# ELECTRO3.net
KiCad netlist of a schematic drawn in Altium Designer
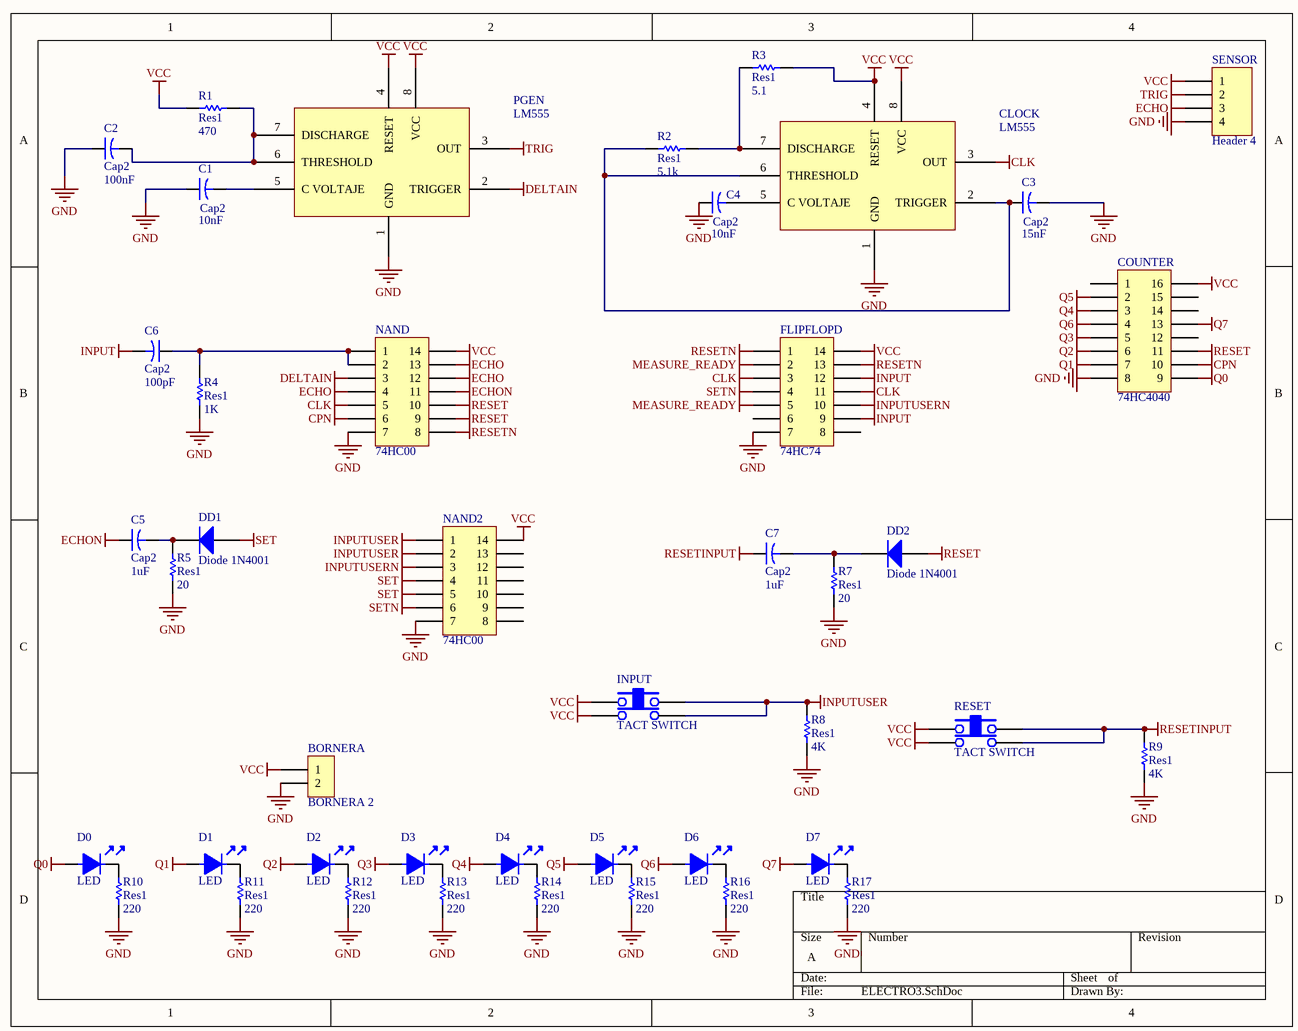
[diagram p0: ELECTRO3.SchDoc]

(export (version "E")
  (design (tool "Eeschema 10.0.6"))
  (components
    (comp (ref "BORNERA")
      (value "BORNERA 2")
      (footprint "BORNERA2")
      (libsource (lib "LIBEBAL") (part "BORNERA 2"))
    )
    (comp (ref "C1")
      (value "Cap2")
      (footprint "CAPR5-4X5")
      (description "Capacitor")
      (fields (field (name "ALTIUM_VALUE") "10nF") (field (name "PUBLISHER") "Altium Limited"))
      (libsource (lib "Miscellaneous Devices") (part "Cap2"))
    )
    (comp (ref "C2")
      (value "Cap2")
      (footprint "CAPR5-4X5")
      (description "Capacitor")
      (fields (field (name "ALTIUM_VALUE") "100nF") (field (name "PUBLISHER") "Altium Limited"))
      (libsource (lib "Miscellaneous Devices") (part "Cap2"))
    )
    (comp (ref "C3")
      (value "Cap2")
      (footprint "CAPR5-4X5")
      (description "Capacitor")
      (fields (field (name "ALTIUM_VALUE") "15nF") (field (name "PUBLISHER") "Altium Limited"))
      (libsource (lib "Miscellaneous Devices") (part "Cap2"))
    )
    (comp (ref "C4")
      (value "Cap2")
      (footprint "CAPR5-4X5")
      (description "Capacitor")
      (fields (field (name "ALTIUM_VALUE") "10nF") (field (name "PUBLISHER") "Altium Limited"))
      (libsource (lib "Miscellaneous Devices") (part "Cap2"))
    )
    (comp (ref "C5")
      (value "Cap2")
      (footprint "CAPR5-4X5")
      (description "Capacitor")
      (fields (field (name "ALTIUM_VALUE") "1uF") (field (name "PUBLISHER") "Altium Limited"))
      (libsource (lib "Miscellaneous Devices") (part "Cap2"))
    )
    (comp (ref "C6")
      (value "Cap2")
      (footprint "CAPR5-4X5")
      (description "Capacitor")
      (fields (field (name "ALTIUM_VALUE") "100pF") (field (name "PUBLISHER") "Altium Limited"))
      (libsource (lib "Miscellaneous Devices") (part "Cap2"))
    )
    (comp (ref "C7")
      (value "Cap2")
      (footprint "CAPR5-4X5")
      (description "Capacitor")
      (fields (field (name "ALTIUM_VALUE") "1uF") (field (name "PUBLISHER") "Altium Limited"))
      (libsource (lib "Miscellaneous Devices") (part "Cap2"))
    )
    (comp (ref "CLOCK")
      (value "LM555")
      (footprint "DIP8")
      (description "Timer")
      (libsource (lib "LIBEBAL") (part "LM555"))
    )
    (comp (ref "COUNTER")
      (value "74HC4040")
      (footprint "DIP16")
      (libsource (lib "LIBEBAL") (part "IC_DIP16"))
    )
    (comp (ref "D0") (value "LED") (footprint "LED3") (libsource (lib "LIBEBAL") (part "LED")))
    (comp (ref "D1") (value "LED") (footprint "LED3") (libsource (lib "LIBEBAL") (part "LED")))
    (comp (ref "D2") (value "LED") (footprint "LED3") (libsource (lib "LIBEBAL") (part "LED")))
    (comp (ref "D3") (value "LED") (footprint "LED3") (libsource (lib "LIBEBAL") (part "LED")))
    (comp (ref "D4") (value "LED") (footprint "LED3") (libsource (lib "LIBEBAL") (part "LED")))
    (comp (ref "D5") (value "LED") (footprint "LED3") (libsource (lib "LIBEBAL") (part "LED")))
    (comp (ref "D6") (value "LED") (footprint "LED3") (libsource (lib "LIBEBAL") (part "LED")))
    (comp (ref "D7") (value "LED") (footprint "LED3") (libsource (lib "LIBEBAL") (part "LED")))
    (comp (ref "DD1")
      (value "Diode 1N4001")
      (footprint "DO-41")
      (description "1 Amp General Purpose Rectifier")
      (fields (field (name "PUBLISHER") "Altium Limited"))
      (libsource (lib "Miscellaneous Devices") (part "Diode 1N4001"))
    )
    (comp (ref "DD2")
      (value "Diode 1N4001")
      (footprint "DO-41")
      (description "1 Amp General Purpose Rectifier")
      (fields (field (name "PUBLISHER") "Altium Limited"))
      (libsource (lib "Miscellaneous Devices") (part "Diode 1N4001"))
    )
    (comp (ref "FLIPFLOPD")
      (value "74HC74")
      (footprint "DIP14")
      (libsource (lib "LIBEBAL") (part "IC_DIP14"))
    )
    (comp (ref "INPUT")
      (value "TACT SWITCH")
      (footprint "TACTSWITCH")
      (libsource (lib "LIBEBAL") (part "TACT SWITCH"))
    )
    (comp (ref "NAND") (value "74HC00") (footprint "DIP14") (libsource (lib "LIBEBAL") (part "IC_DIP14")))
    (comp (ref "NAND2") (value "74HC00") (footprint "DIP14") (libsource (lib "LIBEBAL") (part "IC_DIP14")))
    (comp (ref "PGEN")
      (value "LM555")
      (footprint "DIP8")
      (description "Timer")
      (libsource (lib "LIBEBAL") (part "LM555"))
    )
    (comp (ref "R1")
      (value "Res1")
      (footprint "AXIAL-0.3")
      (description "Resistor")
      (fields (field (name "ALTIUM_VALUE") "470") (field (name "PUBLISHER") "Altium Limited"))
      (libsource (lib "Miscellaneous Devices") (part "Res1"))
    )
    (comp (ref "R2")
      (value "Res1")
      (footprint "AXIAL-0.3")
      (description "Resistor")
      (fields (field (name "ALTIUM_VALUE") "5.1k") (field (name "PUBLISHER") "Altium Limited"))
      (libsource (lib "Miscellaneous Devices") (part "Res1"))
    )
    (comp (ref "R3")
      (value "Res1")
      (footprint "AXIAL-0.3")
      (description "Resistor")
      (fields (field (name "ALTIUM_VALUE") "5.1") (field (name "PUBLISHER") "Altium Limited"))
      (libsource (lib "Miscellaneous Devices") (part "Res1"))
    )
    (comp (ref "R4")
      (value "Res1")
      (footprint "AXIAL-0.3")
      (description "Resistor")
      (fields (field (name "ALTIUM_VALUE") "1K") (field (name "PUBLISHER") "Altium Limited"))
      (libsource (lib "Miscellaneous Devices") (part "Res1"))
    )
    (comp (ref "R5")
      (value "Res1")
      (footprint "AXIAL-0.3")
      (description "Resistor")
      (fields (field (name "ALTIUM_VALUE") "20") (field (name "PUBLISHER") "Altium Limited"))
      (libsource (lib "Miscellaneous Devices") (part "Res1"))
    )
    (comp (ref "R7")
      (value "Res1")
      (footprint "AXIAL-0.3")
      (description "Resistor")
      (fields (field (name "ALTIUM_VALUE") "20") (field (name "PUBLISHER") "Altium Limited"))
      (libsource (lib "Miscellaneous Devices") (part "Res1"))
    )
    (comp (ref "R8")
      (value "Res1")
      (footprint "AXIAL-0.3")
      (description "Resistor")
      (fields (field (name "ALTIUM_VALUE") "4K") (field (name "PUBLISHER") "Altium Limited"))
      (libsource (lib "Miscellaneous Devices") (part "Res1"))
    )
    (comp (ref "R9")
      (value "Res1")
      (footprint "AXIAL-0.3")
      (description "Resistor")
      (fields (field (name "ALTIUM_VALUE") "4K") (field (name "PUBLISHER") "Altium Limited"))
      (libsource (lib "Miscellaneous Devices") (part "Res1"))
    )
    (comp (ref "R10")
      (value "Res1")
      (footprint "AXIAL-0.3")
      (description "Resistor")
      (fields (field (name "ALTIUM_VALUE") "220") (field (name "PUBLISHER") "Altium Limited"))
      (libsource (lib "Miscellaneous Devices") (part "Res1"))
    )
    (comp (ref "R11")
      (value "Res1")
      (footprint "AXIAL-0.3")
      (description "Resistor")
      (fields (field (name "ALTIUM_VALUE") "220") (field (name "PUBLISHER") "Altium Limited"))
      (libsource (lib "Miscellaneous Devices") (part "Res1"))
    )
    (comp (ref "R12")
      (value "Res1")
      (footprint "AXIAL-0.3")
      (description "Resistor")
      (fields (field (name "ALTIUM_VALUE") "220") (field (name "PUBLISHER") "Altium Limited"))
      (libsource (lib "Miscellaneous Devices") (part "Res1"))
    )
    (comp (ref "R13")
      (value "Res1")
      (footprint "AXIAL-0.3")
      (description "Resistor")
      (fields (field (name "ALTIUM_VALUE") "220") (field (name "PUBLISHER") "Altium Limited"))
      (libsource (lib "Miscellaneous Devices") (part "Res1"))
    )
    (comp (ref "R14")
      (value "Res1")
      (footprint "AXIAL-0.3")
      (description "Resistor")
      (fields (field (name "ALTIUM_VALUE") "220") (field (name "PUBLISHER") "Altium Limited"))
      (libsource (lib "Miscellaneous Devices") (part "Res1"))
    )
    (comp (ref "R15")
      (value "Res1")
      (footprint "AXIAL-0.3")
      (description "Resistor")
      (fields (field (name "ALTIUM_VALUE") "220") (field (name "PUBLISHER") "Altium Limited"))
      (libsource (lib "Miscellaneous Devices") (part "Res1"))
    )
    (comp (ref "R16")
      (value "Res1")
      (footprint "AXIAL-0.3")
      (description "Resistor")
      (fields (field (name "ALTIUM_VALUE") "220") (field (name "PUBLISHER") "Altium Limited"))
      (libsource (lib "Miscellaneous Devices") (part "Res1"))
    )
    (comp (ref "R17")
      (value "Res1")
      (footprint "AXIAL-0.3")
      (description "Resistor")
      (fields (field (name "ALTIUM_VALUE") "220") (field (name "PUBLISHER") "Altium Limited"))
      (libsource (lib "Miscellaneous Devices") (part "Res1"))
    )
    (comp (ref "RESET")
      (value "TACT SWITCH")
      (footprint "TACTSWITCH")
      (libsource (lib "LIBEBAL") (part "TACT SWITCH"))
    )
    (comp (ref "SENSOR")
      (value "Header 4")
      (footprint "HDR1X4")
      (description "Header, 4-Pin")
      (fields (field (name "PUBLISHER") "Altium Limited"))
      (libsource (lib "Miscellaneous Connectors") (part "Header 4"))
    )
  )
  (nets
    (net (code "1") (name "CLK") (class "Default")
      (node (ref "CLOCK") (pin "3") (pinfunction "OUT_3") (pintype "passive"))
      (node (ref "FLIPFLOPD") (pin "11") (pinfunction "11_11") (pintype "passive"))
      (node (ref "FLIPFLOPD") (pin "3") (pinfunction "3_3") (pintype "passive"))
      (node (ref "NAND") (pin "5") (pinfunction "5_5") (pintype "passive"))
    )
    (net (code "2") (name "CPN") (class "Default")
      (node (ref "COUNTER") (pin "10") (pinfunction "10_10") (pintype "passive"))
      (node (ref "NAND") (pin "6") (pinfunction "6_6") (pintype "passive"))
    )
    (net (code "3") (name "DELTAIN") (class "Default")
      (node (ref "NAND") (pin "3") (pinfunction "3_3") (pintype "passive"))
      (node (ref "PGEN") (pin "2") (pinfunction "TRIGGER_2") (pintype "passive"))
    )
    (net (code "4") (name "ECHO") (class "Default")
      (node (ref "NAND") (pin "12") (pinfunction "12_12") (pintype "passive"))
      (node (ref "NAND") (pin "13") (pinfunction "13_13") (pintype "passive"))
      (node (ref "NAND") (pin "4") (pinfunction "4_4") (pintype "passive"))
      (node (ref "SENSOR") (pin "3") (pinfunction "3_3") (pintype "passive"))
    )
    (net (code "5") (name "ECHON") (class "Default")
      (node (ref "C5") (pin "1") (pinfunction "1_1") (pintype "passive"))
      (node (ref "NAND") (pin "11") (pinfunction "11_11") (pintype "passive"))
    )
    (net (code "6") (name "GND") (class "Default")
      (node (ref "BORNERA") (pin "2") (pinfunction "2_2") (pintype "passive"))
      (node (ref "C1") (pin "1") (pinfunction "1_1") (pintype "passive"))
      (node (ref "C2") (pin "1") (pinfunction "1_1") (pintype "passive"))
      (node (ref "C3") (pin "2") (pinfunction "2_2") (pintype "passive"))
      (node (ref "C4") (pin "1") (pinfunction "1_1") (pintype "passive"))
      (node (ref "CLOCK") (pin "1") (pinfunction "GND_1") (pintype "passive"))
      (node (ref "COUNTER") (pin "8") (pinfunction "8_8") (pintype "passive"))
      (node (ref "FLIPFLOPD") (pin "7") (pinfunction "7_7") (pintype "passive"))
      (node (ref "NAND") (pin "7") (pinfunction "7_7") (pintype "passive"))
      (node (ref "NAND2") (pin "7") (pinfunction "7_7") (pintype "passive"))
      (node (ref "PGEN") (pin "1") (pinfunction "GND_1") (pintype "passive"))
      (node (ref "R10") (pin "1") (pinfunction "1_1") (pintype "passive"))
      (node (ref "R11") (pin "1") (pinfunction "1_1") (pintype "passive"))
      (node (ref "R12") (pin "1") (pinfunction "1_1") (pintype "passive"))
      (node (ref "R13") (pin "1") (pinfunction "1_1") (pintype "passive"))
      (node (ref "R14") (pin "1") (pinfunction "1_1") (pintype "passive"))
      (node (ref "R15") (pin "1") (pinfunction "1_1") (pintype "passive"))
      (node (ref "R16") (pin "1") (pinfunction "1_1") (pintype "passive"))
      (node (ref "R17") (pin "1") (pinfunction "1_1") (pintype "passive"))
      (node (ref "R4") (pin "2") (pinfunction "2_2") (pintype "passive"))
      (node (ref "R5") (pin "1") (pinfunction "1_1") (pintype "passive"))
      (node (ref "R7") (pin "1") (pinfunction "1_1") (pintype "passive"))
      (node (ref "R8") (pin "1") (pinfunction "1_1") (pintype "passive"))
      (node (ref "R9") (pin "1") (pinfunction "1_1") (pintype "passive"))
      (node (ref "SENSOR") (pin "4") (pinfunction "4_4") (pintype "passive"))
    )
    (net (code "7") (name "INPUT") (class "Default")
      (node (ref "C6") (pin "2") (pinfunction "2_2") (pintype "passive"))
      (node (ref "FLIPFLOPD") (pin "12") (pinfunction "12_12") (pintype "passive"))
      (node (ref "FLIPFLOPD") (pin "9") (pinfunction "9_9") (pintype "passive"))
    )
    (net (code "8") (name "INPUTUSER") (class "Default")
      (node (ref "INPUT") (pin "3") (pinfunction "3_3") (pintype "passive"))
      (node (ref "INPUT") (pin "4") (pinfunction "4_4") (pintype "passive"))
      (node (ref "NAND2") (pin "1") (pinfunction "1_1") (pintype "passive"))
      (node (ref "NAND2") (pin "2") (pinfunction "2_2") (pintype "passive"))
      (node (ref "R8") (pin "2") (pinfunction "2_2") (pintype "passive"))
    )
    (net (code "9") (name "INPUTUSERN") (class "Default")
      (node (ref "FLIPFLOPD") (pin "10") (pinfunction "10_10") (pintype "passive"))
      (node (ref "NAND2") (pin "3") (pinfunction "3_3") (pintype "passive"))
    )
    (net (code "10") (name "MEASURE_READY") (class "Default")
      (node (ref "FLIPFLOPD") (pin "2") (pinfunction "2_2") (pintype "passive"))
      (node (ref "FLIPFLOPD") (pin "5") (pinfunction "5_5") (pintype "passive"))
    )
    (net (code "11") (name "Net-(C6-Pad1)") (class "Default")
      (node (ref "C6") (pin "1") (pinfunction "1_1") (pintype "passive"))
      (node (ref "NAND") (pin "1") (pinfunction "1_1") (pintype "passive"))
      (node (ref "NAND") (pin "2") (pinfunction "2_2") (pintype "passive"))
      (node (ref "R4") (pin "1") (pinfunction "1_1") (pintype "passive"))
    )
    (net (code "12") (name "Net-(CLOCK-C_VOLTAJE)") (class "Default")
      (node (ref "C4") (pin "2") (pinfunction "2_2") (pintype "passive"))
      (node (ref "CLOCK") (pin "5") (pinfunction "C_VOLTAJE_5") (pintype "passive"))
    )
    (net (code "13") (name "Net-(CLOCK-DISCHARGE)") (class "Default")
      (node (ref "CLOCK") (pin "7") (pinfunction "DISCHARGE_7") (pintype "passive"))
      (node (ref "R2") (pin "2") (pinfunction "2_2") (pintype "passive"))
      (node (ref "R3") (pin "1") (pinfunction "1_1") (pintype "passive"))
    )
    (net (code "14") (name "Net-(CLOCK-THRESHOLD)") (class "Default")
      (node (ref "C3") (pin "1") (pinfunction "1_1") (pintype "passive"))
      (node (ref "CLOCK") (pin "2") (pinfunction "TRIGGER_2") (pintype "passive"))
      (node (ref "CLOCK") (pin "6") (pinfunction "THRESHOLD_6") (pintype "passive"))
      (node (ref "R2") (pin "1") (pinfunction "1_1") (pintype "passive"))
    )
    (net (code "15") (name "Net-(D0-Pad2)") (class "Default")
      (node (ref "D0") (pin "2") (pinfunction "2_2") (pintype "passive"))
      (node (ref "R10") (pin "2") (pinfunction "2_2") (pintype "passive"))
    )
    (net (code "16") (name "Net-(D1-Pad2)") (class "Default")
      (node (ref "D1") (pin "2") (pinfunction "2_2") (pintype "passive"))
      (node (ref "R11") (pin "2") (pinfunction "2_2") (pintype "passive"))
    )
    (net (code "17") (name "Net-(D2-Pad2)") (class "Default")
      (node (ref "D2") (pin "2") (pinfunction "2_2") (pintype "passive"))
      (node (ref "R12") (pin "2") (pinfunction "2_2") (pintype "passive"))
    )
    (net (code "18") (name "Net-(D3-Pad2)") (class "Default")
      (node (ref "D3") (pin "2") (pinfunction "2_2") (pintype "passive"))
      (node (ref "R13") (pin "2") (pinfunction "2_2") (pintype "passive"))
    )
    (net (code "19") (name "Net-(D4-Pad2)") (class "Default")
      (node (ref "D4") (pin "2") (pinfunction "2_2") (pintype "passive"))
      (node (ref "R14") (pin "2") (pinfunction "2_2") (pintype "passive"))
    )
    (net (code "20") (name "Net-(D5-Pad2)") (class "Default")
      (node (ref "D5") (pin "2") (pinfunction "2_2") (pintype "passive"))
      (node (ref "R15") (pin "2") (pinfunction "2_2") (pintype "passive"))
    )
    (net (code "21") (name "Net-(D6-Pad2)") (class "Default")
      (node (ref "D6") (pin "2") (pinfunction "2_2") (pintype "passive"))
      (node (ref "R16") (pin "2") (pinfunction "2_2") (pintype "passive"))
    )
    (net (code "22") (name "Net-(D7-Pad2)") (class "Default")
      (node (ref "D7") (pin "2") (pinfunction "2_2") (pintype "passive"))
      (node (ref "R17") (pin "2") (pinfunction "2_2") (pintype "passive"))
    )
    (net (code "23") (name "Net-(DD1-K)") (class "Default")
      (node (ref "C5") (pin "2") (pinfunction "2_2") (pintype "passive"))
      (node (ref "DD1") (pin "2") (pinfunction "K_2") (pintype "passive"))
      (node (ref "R5") (pin "2") (pinfunction "2_2") (pintype "passive"))
    )
    (net (code "24") (name "Net-(DD2-K)") (class "Default")
      (node (ref "C7") (pin "2") (pinfunction "2_2") (pintype "passive"))
      (node (ref "DD2") (pin "2") (pinfunction "K_2") (pintype "passive"))
      (node (ref "R7") (pin "2") (pinfunction "2_2") (pintype "passive"))
    )
    (net (code "25") (name "Net-(PGEN-C_VOLTAJE)") (class "Default")
      (node (ref "C1") (pin "2") (pinfunction "2_2") (pintype "passive"))
      (node (ref "PGEN") (pin "5") (pinfunction "C_VOLTAJE_5") (pintype "passive"))
    )
    (net (code "26") (name "Net-(PGEN-DISCHARGE)") (class "Default")
      (node (ref "C2") (pin "2") (pinfunction "2_2") (pintype "passive"))
      (node (ref "PGEN") (pin "6") (pinfunction "THRESHOLD_6") (pintype "passive"))
      (node (ref "PGEN") (pin "7") (pinfunction "DISCHARGE_7") (pintype "passive"))
      (node (ref "R1") (pin "2") (pinfunction "2_2") (pintype "passive"))
    )
    (net (code "27") (name "Q0") (class "Default")
      (node (ref "COUNTER") (pin "9") (pinfunction "9_9") (pintype "passive"))
      (node (ref "D0") (pin "1") (pinfunction "1_1") (pintype "passive"))
    )
    (net (code "28") (name "Q1") (class "Default")
      (node (ref "COUNTER") (pin "7") (pinfunction "7_7") (pintype "passive"))
      (node (ref "D1") (pin "1") (pinfunction "1_1") (pintype "passive"))
    )
    (net (code "29") (name "Q2") (class "Default")
      (node (ref "COUNTER") (pin "6") (pinfunction "6_6") (pintype "passive"))
      (node (ref "D2") (pin "1") (pinfunction "1_1") (pintype "passive"))
    )
    (net (code "30") (name "Q3") (class "Default")
      (node (ref "COUNTER") (pin "5") (pinfunction "5_5") (pintype "passive"))
      (node (ref "D3") (pin "1") (pinfunction "1_1") (pintype "passive"))
    )
    (net (code "31") (name "Q4") (class "Default")
      (node (ref "COUNTER") (pin "3") (pinfunction "3_3") (pintype "passive"))
      (node (ref "D4") (pin "1") (pinfunction "1_1") (pintype "passive"))
    )
    (net (code "32") (name "Q5") (class "Default")
      (node (ref "COUNTER") (pin "2") (pinfunction "2_2") (pintype "passive"))
      (node (ref "D5") (pin "1") (pinfunction "1_1") (pintype "passive"))
    )
    (net (code "33") (name "Q6") (class "Default")
      (node (ref "COUNTER") (pin "4") (pinfunction "4_4") (pintype "passive"))
      (node (ref "D6") (pin "1") (pinfunction "1_1") (pintype "passive"))
    )
    (net (code "34") (name "Q7") (class "Default")
      (node (ref "COUNTER") (pin "13") (pinfunction "13_13") (pintype "passive"))
      (node (ref "D7") (pin "1") (pinfunction "1_1") (pintype "passive"))
    )
    (net (code "35") (name "RESET") (class "Default")
      (node (ref "COUNTER") (pin "11") (pinfunction "11_11") (pintype "passive"))
      (node (ref "DD2") (pin "1") (pinfunction "A_1") (pintype "passive"))
      (node (ref "NAND") (pin "10") (pinfunction "10_10") (pintype "passive"))
      (node (ref "NAND") (pin "9") (pinfunction "9_9") (pintype "passive"))
    )
    (net (code "36") (name "RESETINPUT") (class "Default")
      (node (ref "C7") (pin "1") (pinfunction "1_1") (pintype "passive"))
      (node (ref "R9") (pin "2") (pinfunction "2_2") (pintype "passive"))
      (node (ref "RESET") (pin "3") (pinfunction "3_3") (pintype "passive"))
      (node (ref "RESET") (pin "4") (pinfunction "4_4") (pintype "passive"))
    )
    (net (code "37") (name "RESETN") (class "Default")
      (node (ref "FLIPFLOPD") (pin "1") (pinfunction "1_1") (pintype "passive"))
      (node (ref "FLIPFLOPD") (pin "13") (pinfunction "13_13") (pintype "passive"))
      (node (ref "NAND") (pin "8") (pinfunction "8_8") (pintype "passive"))
    )
    (net (code "38") (name "SET") (class "Default")
      (node (ref "DD1") (pin "1") (pinfunction "A_1") (pintype "passive"))
      (node (ref "NAND2") (pin "4") (pinfunction "4_4") (pintype "passive"))
      (node (ref "NAND2") (pin "5") (pinfunction "5_5") (pintype "passive"))
    )
    (net (code "39") (name "SETN") (class "Default")
      (node (ref "FLIPFLOPD") (pin "4") (pinfunction "4_4") (pintype "passive"))
      (node (ref "NAND2") (pin "6") (pinfunction "6_6") (pintype "passive"))
    )
    (net (code "40") (name "TRIG") (class "Default")
      (node (ref "PGEN") (pin "3") (pinfunction "OUT_3") (pintype "passive"))
      (node (ref "SENSOR") (pin "2") (pinfunction "2_2") (pintype "passive"))
    )
    (net (code "41") (name "VCC") (class "Default")
      (node (ref "BORNERA") (pin "1") (pinfunction "1_1") (pintype "passive"))
      (node (ref "CLOCK") (pin "4") (pinfunction "RESET_4") (pintype "passive"))
      (node (ref "CLOCK") (pin "8") (pinfunction "VCC_8") (pintype "passive"))
      (node (ref "COUNTER") (pin "16") (pinfunction "16_16") (pintype "passive"))
      (node (ref "FLIPFLOPD") (pin "14") (pinfunction "14_14") (pintype "passive"))
      (node (ref "INPUT") (pin "1") (pinfunction "1_1") (pintype "passive"))
      (node (ref "INPUT") (pin "2") (pinfunction "2_2") (pintype "passive"))
      (node (ref "NAND") (pin "14") (pinfunction "14_14") (pintype "passive"))
      (node (ref "NAND2") (pin "14") (pinfunction "14_14") (pintype "passive"))
      (node (ref "PGEN") (pin "4") (pinfunction "RESET_4") (pintype "passive"))
      (node (ref "PGEN") (pin "8") (pinfunction "VCC_8") (pintype "passive"))
      (node (ref "R1") (pin "1") (pinfunction "1_1") (pintype "passive"))
      (node (ref "R3") (pin "2") (pinfunction "2_2") (pintype "passive"))
      (node (ref "RESET") (pin "1") (pinfunction "1_1") (pintype "passive"))
      (node (ref "RESET") (pin "2") (pinfunction "2_2") (pintype "passive"))
      (node (ref "SENSOR") (pin "1") (pinfunction "1_1") (pintype "passive"))
    )
    (net (code "42") (name "unconnected-(COUNTER-Pad1)") (class "Default")
      (node (ref "COUNTER") (pin "1") (pinfunction "1_1") (pintype "passive"))
    )
    (net (code "43") (name "unconnected-(COUNTER-Pad12)") (class "Default")
      (node (ref "COUNTER") (pin "12") (pinfunction "12_12") (pintype "passive"))
    )
    (net (code "44") (name "unconnected-(COUNTER-Pad14)") (class "Default")
      (node (ref "COUNTER") (pin "14") (pinfunction "14_14") (pintype "passive"))
    )
    (net (code "45") (name "unconnected-(COUNTER-Pad15)") (class "Default")
      (node (ref "COUNTER") (pin "15") (pinfunction "15_15") (pintype "passive"))
    )
    (net (code "46") (name "unconnected-(FLIPFLOPD-Pad6)") (class "Default")
      (node (ref "FLIPFLOPD") (pin "6") (pinfunction "6_6") (pintype "passive"))
    )
    (net (code "47") (name "unconnected-(FLIPFLOPD-Pad8)") (class "Default")
      (node (ref "FLIPFLOPD") (pin "8") (pinfunction "8_8") (pintype "passive"))
    )
    (net (code "48") (name "unconnected-(NAND2-Pad8)") (class "Default")
      (node (ref "NAND2") (pin "8") (pinfunction "8_8") (pintype "passive"))
    )
    (net (code "49") (name "unconnected-(NAND2-Pad9)") (class "Default")
      (node (ref "NAND2") (pin "9") (pinfunction "9_9") (pintype "passive"))
    )
    (net (code "50") (name "unconnected-(NAND2-Pad10)") (class "Default")
      (node (ref "NAND2") (pin "10") (pinfunction "10_10") (pintype "passive"))
    )
    (net (code "51") (name "unconnected-(NAND2-Pad11)") (class "Default")
      (node (ref "NAND2") (pin "11") (pinfunction "11_11") (pintype "passive"))
    )
    (net (code "52") (name "unconnected-(NAND2-Pad12)") (class "Default")
      (node (ref "NAND2") (pin "12") (pinfunction "12_12") (pintype "passive"))
    )
    (net (code "53") (name "unconnected-(NAND2-Pad13)") (class "Default")
      (node (ref "NAND2") (pin "13") (pinfunction "13_13") (pintype "passive"))
    )
  )
)
